# ShieldHeltec_WS.net
KiCad netlist of a schematic drawn in EasyEDA
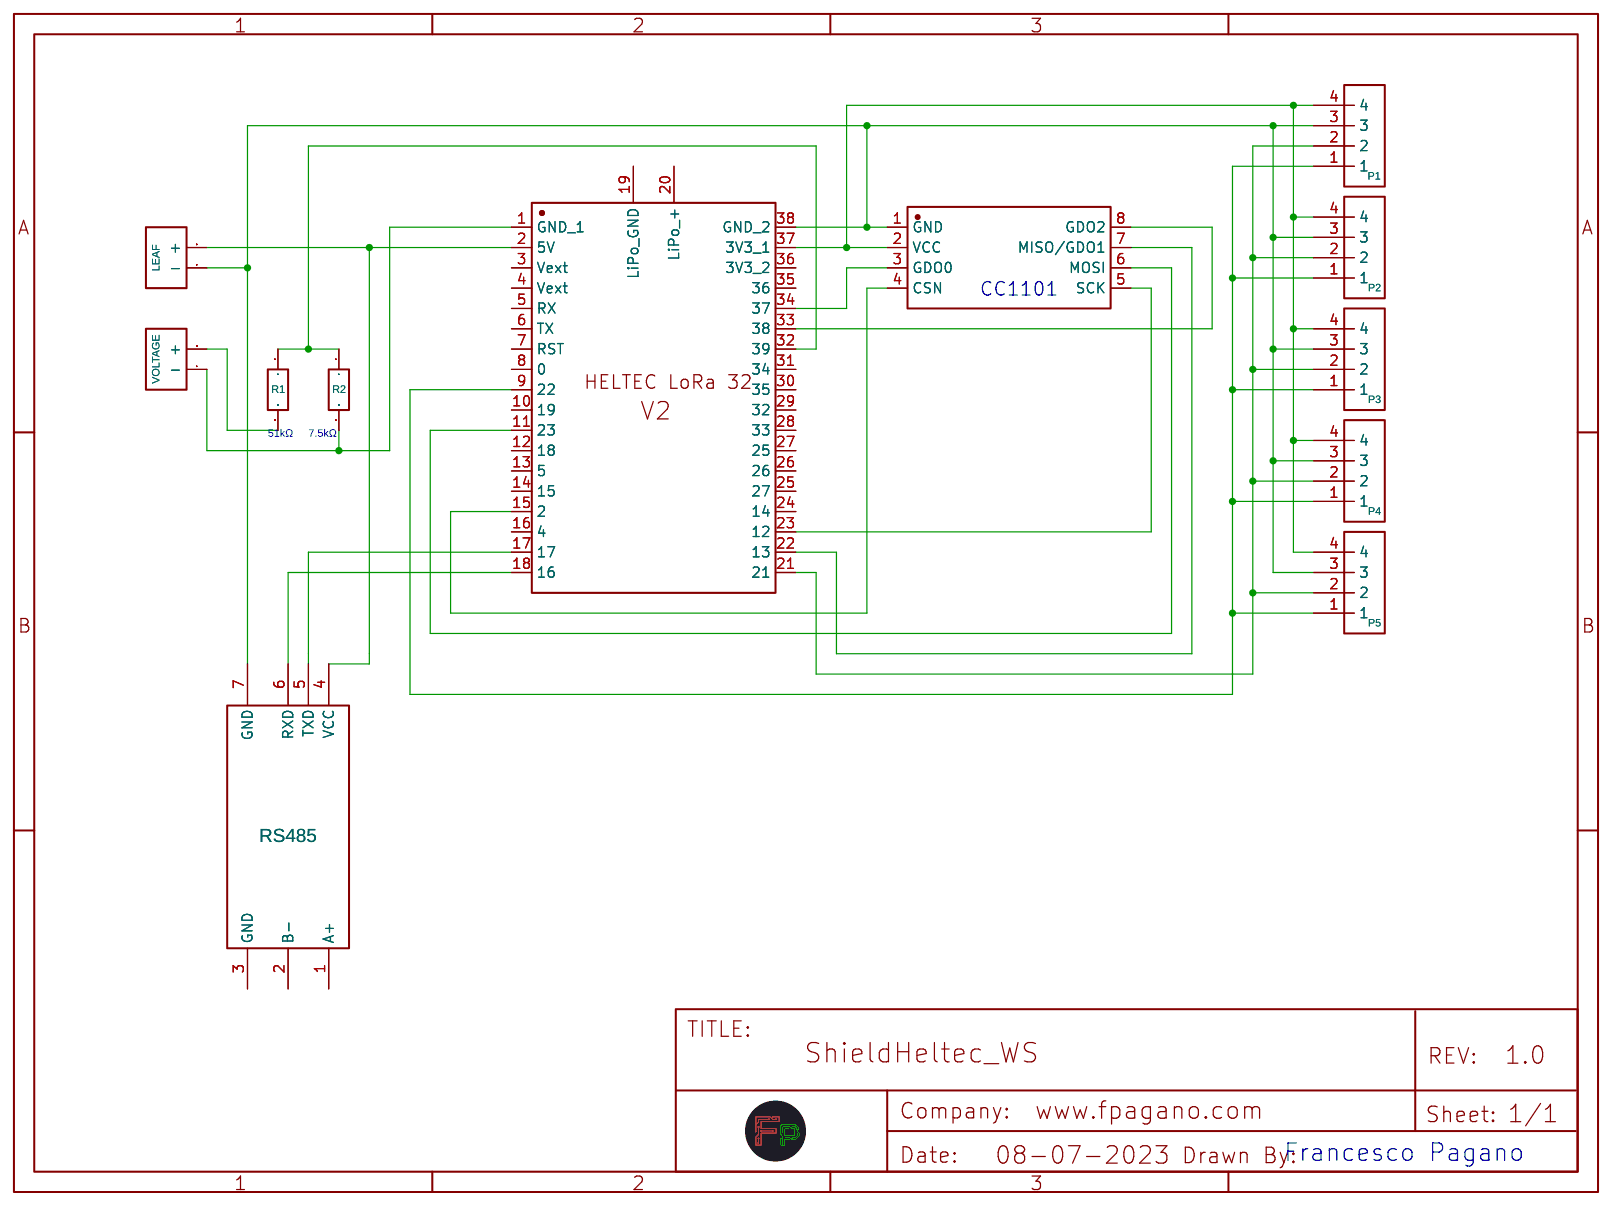
[diagram p0: schematic sheet]

(export (version "E")
  (design (tool "Eeschema 10.0.6"))
  (components
    (comp (ref "CC1_") (value "CC1101 Module") (libsource (lib "") (part "CC1101 Module")))
    (comp (ref "LEAF") (value "Foglia") (libsource (lib "") (part "CONN-TH_2P-P5.00")))
    (comp (ref "P1") (value "Header 4 Pin 2.54mm") (libsource (lib "") (part "Pin_Header_Female_4PIN")))
    (comp (ref "P2") (value "Header 4 Pin 2.54mm") (libsource (lib "") (part "Pin_Header_Female_4PIN")))
    (comp (ref "P3") (value "Header 4 Pin 2.54mm") (libsource (lib "") (part "Pin_Header_Female_4PIN")))
    (comp (ref "P4") (value "Header 4 Pin 2.54mm") (libsource (lib "") (part "Pin_Header_Female_4PIN")))
    (comp (ref "P5") (value "Header 4 Pin 2.54mm") (libsource (lib "") (part "Pin_Header_Female_4PIN")))
    (comp (ref "R1") (value "R1") (libsource (lib "") (part "R_AXIAL-0.5_EU")))
    (comp (ref "R2") (value "R2") (libsource (lib "") (part "R_AXIAL-0.5_EU")))
    (comp (ref "U2")
      (value "HELTEC_LORA_ESP32_V2")
      (fields (field (name "Manufacturer Part") "WIFI LoRa 32"))
      (libsource (lib "") (part "HELTEC_LORA_ESP32_V2"))
    )
    (comp (ref "U4") (value "RS485") (libsource (lib "") (part "01.RS485 TO TTL 5V 3.3V")))
    (comp (ref "VOLTAGE") (value "Foglia") (libsource (lib "") (part "CONN-TH_2P-P5.00_1")))
  )
  (nets
    (net (code "1") (name "Net-(CC1_-CSN)") (class "Default")
      (node (ref "CC1_") (pin "4") (pinfunction "CSN_4") (pintype "unspecified"))
      (node (ref "U2") (pin "15") (pinfunction "2_15") (pintype "unspecified"))
    )
    (net (code "2") (name "Net-(CC1_-GDO0)") (class "Default")
      (node (ref "CC1_") (pin "3") (pinfunction "GDO0_3") (pintype "unspecified"))
      (node (ref "U2") (pin "34") (pinfunction "37_34") (pintype "unspecified"))
    )
    (net (code "3") (name "Net-(CC1_-GDO2)") (class "Default")
      (node (ref "CC1_") (pin "8") (pinfunction "GDO2_8") (pintype "unspecified"))
      (node (ref "U2") (pin "33") (pinfunction "38_33") (pintype "unspecified"))
    )
    (net (code "4") (name "Net-(CC1_-GND)") (class "Default")
      (node (ref "CC1_") (pin "1") (pinfunction "GND_1") (pintype "unspecified"))
      (node (ref "LEAF") (pin "1") (pinfunction "-_1") (pintype "unspecified"))
      (node (ref "P1") (pin "3") (pinfunction "3_3") (pintype "unspecified"))
      (node (ref "P2") (pin "3") (pinfunction "3_3") (pintype "unspecified"))
      (node (ref "P3") (pin "3") (pinfunction "3_3") (pintype "unspecified"))
      (node (ref "P4") (pin "3") (pinfunction "3_3") (pintype "unspecified"))
      (node (ref "P5") (pin "3") (pinfunction "3_3") (pintype "unspecified"))
      (node (ref "U2") (pin "38") (pinfunction "GND_2_38") (pintype "unspecified"))
      (node (ref "U4") (pin "7") (pinfunction "GND_7") (pintype "unspecified"))
    )
    (net (code "5") (name "Net-(CC1_-MISO{slash}GDO1)") (class "Default")
      (node (ref "CC1_") (pin "7") (pinfunction "MISO/GDO1_7") (pintype "unspecified"))
      (node (ref "U2") (pin "22") (pinfunction "13_22") (pintype "unspecified"))
    )
    (net (code "6") (name "Net-(CC1_-MOSI)") (class "Default")
      (node (ref "CC1_") (pin "6") (pinfunction "MOSI_6") (pintype "unspecified"))
      (node (ref "U2") (pin "11") (pinfunction "23_11") (pintype "unspecified"))
    )
    (net (code "7") (name "Net-(CC1_-SCK)") (class "Default")
      (node (ref "CC1_") (pin "5") (pinfunction "SCK_5") (pintype "unspecified"))
      (node (ref "U2") (pin "23") (pinfunction "12_23") (pintype "unspecified"))
    )
    (net (code "8") (name "Net-(CC1_-VCC)") (class "Default")
      (node (ref "CC1_") (pin "2") (pinfunction "VCC_2") (pintype "unspecified"))
      (node (ref "P1") (pin "4") (pinfunction "4_4") (pintype "unspecified"))
      (node (ref "P2") (pin "4") (pinfunction "4_4") (pintype "unspecified"))
      (node (ref "P3") (pin "4") (pinfunction "4_4") (pintype "unspecified"))
      (node (ref "P4") (pin "4") (pinfunction "4_4") (pintype "unspecified"))
      (node (ref "P5") (pin "4") (pinfunction "4_4") (pintype "unspecified"))
      (node (ref "U2") (pin "37") (pinfunction "3V3_1_37") (pintype "unspecified"))
    )
    (net (code "9") (name "Net-(LEAF-+)") (class "Default")
      (node (ref "LEAF") (pin "2") (pinfunction "+_2") (pintype "unspecified"))
      (node (ref "U2") (pin "2") (pinfunction "5V_2") (pintype "unspecified"))
      (node (ref "U4") (pin "4") (pinfunction "VCC_4") (pintype "unspecified"))
    )
    (net (code "10") (name "Net-(P1-Pad2)") (class "Default")
      (node (ref "P1") (pin "2") (pinfunction "2_2") (pintype "unspecified"))
      (node (ref "P2") (pin "2") (pinfunction "2_2") (pintype "unspecified"))
      (node (ref "P3") (pin "2") (pinfunction "2_2") (pintype "unspecified"))
      (node (ref "P4") (pin "2") (pinfunction "2_2") (pintype "unspecified"))
      (node (ref "P5") (pin "2") (pinfunction "2_2") (pintype "unspecified"))
      (node (ref "U2") (pin "21") (pinfunction "21_21") (pintype "unspecified"))
    )
    (net (code "11") (name "Net-(U2-16)") (class "Default")
      (node (ref "U2") (pin "18") (pinfunction "16_18") (pintype "unspecified"))
      (node (ref "U4") (pin "6") (pinfunction "RXD_6") (pintype "unspecified"))
    )
    (net (code "12") (name "Net-(U2-22)") (class "Default")
      (node (ref "P1") (pin "1") (pinfunction "1_1") (pintype "unspecified"))
      (node (ref "P2") (pin "1") (pinfunction "1_1") (pintype "unspecified"))
      (node (ref "P3") (pin "1") (pinfunction "1_1") (pintype "unspecified"))
      (node (ref "P4") (pin "1") (pinfunction "1_1") (pintype "unspecified"))
      (node (ref "P5") (pin "1") (pinfunction "1_1") (pintype "unspecified"))
      (node (ref "U2") (pin "9") (pinfunction "22_9") (pintype "unspecified"))
    )
    (net (code "13") (name "Net-(U2-39)") (class "Default")
      (node (ref "R1") (pin "1") (pinfunction "1_1") (pintype "unspecified"))
      (node (ref "R2") (pin "1") (pinfunction "1_1") (pintype "unspecified"))
      (node (ref "U2") (pin "32") (pinfunction "39_32") (pintype "unspecified"))
    )
    (net (code "14") (name "Net-(U2-GND_1)") (class "Default")
      (node (ref "R2") (pin "2") (pinfunction "2_2") (pintype "unspecified"))
      (node (ref "U2") (pin "1") (pinfunction "GND_1_1") (pintype "unspecified"))
      (node (ref "VOLTAGE") (pin "1") (pinfunction "-_1") (pintype "unspecified"))
    )
    (net (code "15") (name "Net-(U4-TXD)") (class "Default")
      (node (ref "U2") (pin "17") (pinfunction "17_17") (pintype "unspecified"))
      (node (ref "U4") (pin "5") (pinfunction "TXD_5") (pintype "unspecified"))
    )
    (net (code "16") (name "Net-(VOLTAGE-+)") (class "Default")
      (node (ref "R1") (pin "2") (pinfunction "2_2") (pintype "unspecified"))
      (node (ref "VOLTAGE") (pin "2") (pinfunction "+_2") (pintype "unspecified"))
    )
    (net (code "17") (name "unconnected-(U2-0-Pad8)") (class "Default")
      (node (ref "U2") (pin "8") (pinfunction "0_8") (pintype "unspecified"))
    )
    (net (code "18") (name "unconnected-(U2-3V3_2-Pad36)") (class "Default")
      (node (ref "U2") (pin "36") (pinfunction "3V3_2_36") (pintype "unspecified"))
    )
    (net (code "19") (name "unconnected-(U2-4-Pad16)") (class "Default")
      (node (ref "U2") (pin "16") (pinfunction "4_16") (pintype "unspecified"))
    )
    (net (code "20") (name "unconnected-(U2-5-Pad13)") (class "Default")
      (node (ref "U2") (pin "13") (pinfunction "5_13") (pintype "unspecified"))
    )
    (net (code "21") (name "unconnected-(U2-14-Pad24)") (class "Default")
      (node (ref "U2") (pin "24") (pinfunction "14_24") (pintype "unspecified"))
    )
    (net (code "22") (name "unconnected-(U2-15-Pad14)") (class "Default")
      (node (ref "U2") (pin "14") (pinfunction "15_14") (pintype "unspecified"))
    )
    (net (code "23") (name "unconnected-(U2-18-Pad12)") (class "Default")
      (node (ref "U2") (pin "12") (pinfunction "18_12") (pintype "unspecified"))
    )
    (net (code "24") (name "unconnected-(U2-19-Pad10)") (class "Default")
      (node (ref "U2") (pin "10") (pinfunction "19_10") (pintype "unspecified"))
    )
    (net (code "25") (name "unconnected-(U2-25-Pad27)") (class "Default")
      (node (ref "U2") (pin "27") (pinfunction "25_27") (pintype "unspecified"))
    )
    (net (code "26") (name "unconnected-(U2-27-Pad25)") (class "Default")
      (node (ref "U2") (pin "25") (pinfunction "27_25") (pintype "unspecified"))
    )
    (net (code "27") (name "unconnected-(U2-32-Pad29)") (class "Default")
      (node (ref "U2") (pin "29") (pinfunction "32_29") (pintype "unspecified"))
    )
    (net (code "28") (name "unconnected-(U2-33-Pad28)") (class "Default")
      (node (ref "U2") (pin "28") (pinfunction "33_28") (pintype "unspecified"))
    )
    (net (code "29") (name "unconnected-(U2-34-Pad31)") (class "Default")
      (node (ref "U2") (pin "31") (pinfunction "34_31") (pintype "unspecified"))
    )
    (net (code "30") (name "unconnected-(U2-35-Pad30)") (class "Default")
      (node (ref "U2") (pin "30") (pinfunction "35_30") (pintype "unspecified"))
    )
    (net (code "31") (name "unconnected-(U2-36-Pad35)") (class "Default")
      (node (ref "U2") (pin "35") (pinfunction "36_35") (pintype "unspecified"))
    )
    (net (code "32") (name "unconnected-(U2-LiPo_+-Pad20)") (class "Default")
      (node (ref "U2") (pin "20") (pinfunction "LiPo_+_20") (pintype "unspecified"))
    )
    (net (code "33") (name "unconnected-(U2-LiPo_GND-Pad19)") (class "Default")
      (node (ref "U2") (pin "19") (pinfunction "LiPo_GND_19") (pintype "unspecified"))
    )
    (net (code "34") (name "unconnected-(U2-Pad26)") (class "Default")
      (node (ref "U2") (pin "26") (pinfunction "26_26") (pintype "unspecified"))
    )
    (net (code "35") (name "unconnected-(U2-RST-Pad7)") (class "Default")
      (node (ref "U2") (pin "7") (pinfunction "RST_7") (pintype "unspecified"))
    )
    (net (code "36") (name "unconnected-(U2-RX-Pad5)") (class "Default")
      (node (ref "U2") (pin "5") (pinfunction "RX_5") (pintype "unspecified"))
    )
    (net (code "37") (name "unconnected-(U2-TX-Pad6)") (class "Default")
      (node (ref "U2") (pin "6") (pinfunction "TX_6") (pintype "unspecified"))
    )
    (net (code "38") (name "unconnected-(U2-Vext-Pad3)") (class "Default")
      (node (ref "U2") (pin "3") (pinfunction "Vext_3") (pintype "unspecified"))
    )
    (net (code "39") (name "unconnected-(U2-Vext-Pad4)") (class "Default")
      (node (ref "U2") (pin "4") (pinfunction "Vext_4") (pintype "unspecified"))
    )
    (net (code "40") (name "unconnected-(U4-A+-Pad1)") (class "Default")
      (node (ref "U4") (pin "1") (pinfunction "A+_1") (pintype "unspecified"))
    )
    (net (code "41") (name "unconnected-(U4-B--Pad2)") (class "Default")
      (node (ref "U4") (pin "2") (pinfunction "B-_2") (pintype "unspecified"))
    )
    (net (code "42") (name "unconnected-(U4-GND-Pad3)") (class "Default")
      (node (ref "U4") (pin "3") (pinfunction "GND_3") (pintype "unspecified"))
    )
  )
)
